# p1_led_adapter.net
KiCad netlist of a schematic drawn in Altium Designer
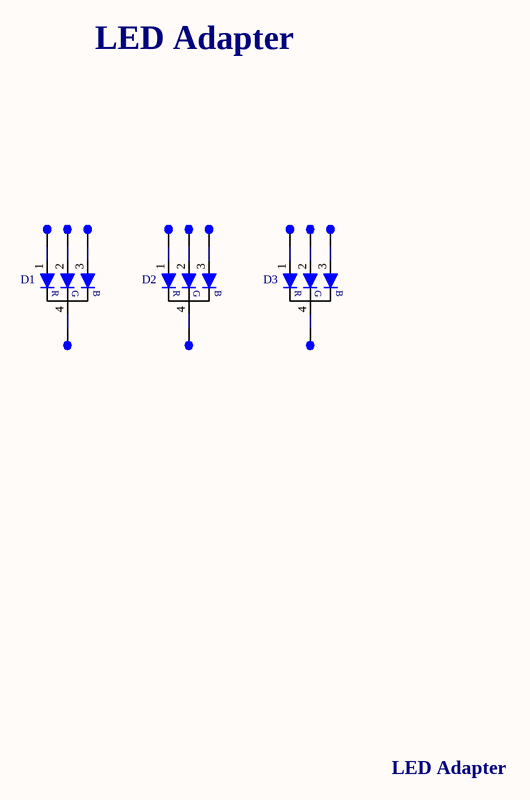
[diagram p0: p1_led_adapter.SchDoc]

(export (version "E")
  (design (tool "Eeschema 10.0.6"))
  (components
    (comp (ref "D1")
      (value "XZM2CRKM2DGFBB45SCCB")
      (footprint "SUN_PLCC4")
      (description "LED RGB CLEAR 4PLCC SMD")
      (fields (field (name "MANUFACTURER") "SunLED") (field (name "PUBLISHER") "Altium Limited"))
      (libsource (lib "Diodes") (part "RGB LED"))
    )
    (comp (ref "D2")
      (value "XZM2CRKM2DGFBB45SCCB")
      (footprint "SUN_PLCC4")
      (description "LED RGB CLEAR 4PLCC SMD")
      (fields (field (name "MANUFACTURER") "SunLED") (field (name "PUBLISHER") "Altium Limited"))
      (libsource (lib "Diodes") (part "RGB LED"))
    )
    (comp (ref "D3")
      (value "XZM2CRKM2DGFBB45SCCB")
      (footprint "SUN_PLCC4")
      (description "LED RGB CLEAR 4PLCC SMD")
      (fields (field (name "MANUFACTURER") "SunLED") (field (name "PUBLISHER") "Altium Limited"))
      (libsource (lib "Diodes") (part "RGB LED"))
    )
    (comp (ref "TP1")
      (value "PTH Test Point")
      (footprint "TP_PTH")
      (description "Test Point")
      (libsource (lib "Misc") (part "PTH Test Point"))
    )
    (comp (ref "TP2")
      (value "PTH Test Point")
      (footprint "TP_PTH")
      (description "Test Point")
      (libsource (lib "Misc") (part "PTH Test Point"))
    )
    (comp (ref "TP3")
      (value "PTH Test Point")
      (footprint "TP_PTH")
      (description "Test Point")
      (libsource (lib "Misc") (part "PTH Test Point"))
    )
    (comp (ref "TP4")
      (value "PTH Test Point")
      (footprint "TP_PTH")
      (description "Test Point")
      (libsource (lib "Misc") (part "PTH Test Point"))
    )
    (comp (ref "TP5")
      (value "PTH Test Point")
      (footprint "TP_PTH")
      (description "Test Point")
      (libsource (lib "Misc") (part "PTH Test Point"))
    )
    (comp (ref "TP6")
      (value "PTH Test Point")
      (footprint "TP_PTH")
      (description "Test Point")
      (libsource (lib "Misc") (part "PTH Test Point"))
    )
    (comp (ref "TP7")
      (value "PTH Test Point")
      (footprint "TP_PTH")
      (description "Test Point")
      (libsource (lib "Misc") (part "PTH Test Point"))
    )
    (comp (ref "TP8")
      (value "PTH Test Point")
      (footprint "TP_PTH")
      (description "Test Point")
      (libsource (lib "Misc") (part "PTH Test Point"))
    )
    (comp (ref "TP9")
      (value "PTH Test Point")
      (footprint "TP_PTH")
      (description "Test Point")
      (libsource (lib "Misc") (part "PTH Test Point"))
    )
    (comp (ref "TP10")
      (value "PTH Test Point")
      (footprint "TP_PTH")
      (description "Test Point")
      (libsource (lib "Misc") (part "PTH Test Point"))
    )
    (comp (ref "TP11")
      (value "PTH Test Point")
      (footprint "TP_PTH")
      (description "Test Point")
      (libsource (lib "Misc") (part "PTH Test Point"))
    )
    (comp (ref "TP12")
      (value "PTH Test Point")
      (footprint "TP_PTH")
      (description "Test Point")
      (libsource (lib "Misc") (part "PTH Test Point"))
    )
  )
  (nets
    (net (code "1") (name "Net-(D1-A1)") (class "Default")
      (node (ref "D1") (pin "1") (pinfunction "A1_1") (pintype "passive"))
      (node (ref "TP1") (pin "1") (pinfunction "1_1") (pintype "passive"))
    )
    (net (code "2") (name "Net-(D1-A2)") (class "Default")
      (node (ref "D1") (pin "2") (pinfunction "A2_2") (pintype "passive"))
      (node (ref "TP2") (pin "1") (pinfunction "1_1") (pintype "passive"))
    )
    (net (code "3") (name "Net-(D1-A3)") (class "Default")
      (node (ref "D1") (pin "3") (pinfunction "A3_3") (pintype "passive"))
      (node (ref "TP3") (pin "1") (pinfunction "1_1") (pintype "passive"))
    )
    (net (code "4") (name "Net-(D1-K)") (class "Default")
      (node (ref "D1") (pin "4") (pinfunction "K_4") (pintype "passive"))
      (node (ref "TP10") (pin "1") (pinfunction "1_1") (pintype "passive"))
    )
    (net (code "5") (name "Net-(D2-A1)") (class "Default")
      (node (ref "D2") (pin "1") (pinfunction "A1_1") (pintype "passive"))
      (node (ref "TP4") (pin "1") (pinfunction "1_1") (pintype "passive"))
    )
    (net (code "6") (name "Net-(D2-A2)") (class "Default")
      (node (ref "D2") (pin "2") (pinfunction "A2_2") (pintype "passive"))
      (node (ref "TP5") (pin "1") (pinfunction "1_1") (pintype "passive"))
    )
    (net (code "7") (name "Net-(D2-A3)") (class "Default")
      (node (ref "D2") (pin "3") (pinfunction "A3_3") (pintype "passive"))
      (node (ref "TP6") (pin "1") (pinfunction "1_1") (pintype "passive"))
    )
    (net (code "8") (name "Net-(D2-K)") (class "Default")
      (node (ref "D2") (pin "4") (pinfunction "K_4") (pintype "passive"))
      (node (ref "TP11") (pin "1") (pinfunction "1_1") (pintype "passive"))
    )
    (net (code "9") (name "Net-(D3-A1)") (class "Default")
      (node (ref "D3") (pin "1") (pinfunction "A1_1") (pintype "passive"))
      (node (ref "TP7") (pin "1") (pinfunction "1_1") (pintype "passive"))
    )
    (net (code "10") (name "Net-(D3-A2)") (class "Default")
      (node (ref "D3") (pin "2") (pinfunction "A2_2") (pintype "passive"))
      (node (ref "TP8") (pin "1") (pinfunction "1_1") (pintype "passive"))
    )
    (net (code "11") (name "Net-(D3-A3)") (class "Default")
      (node (ref "D3") (pin "3") (pinfunction "A3_3") (pintype "passive"))
      (node (ref "TP9") (pin "1") (pinfunction "1_1") (pintype "passive"))
    )
    (net (code "12") (name "Net-(D3-K)") (class "Default")
      (node (ref "D3") (pin "4") (pinfunction "K_4") (pintype "passive"))
      (node (ref "TP12") (pin "1") (pinfunction "1_1") (pintype "passive"))
    )
  )
)
